# BigLCD_final_rev02.net
KiCad netlist of a schematic drawn in EAGLE
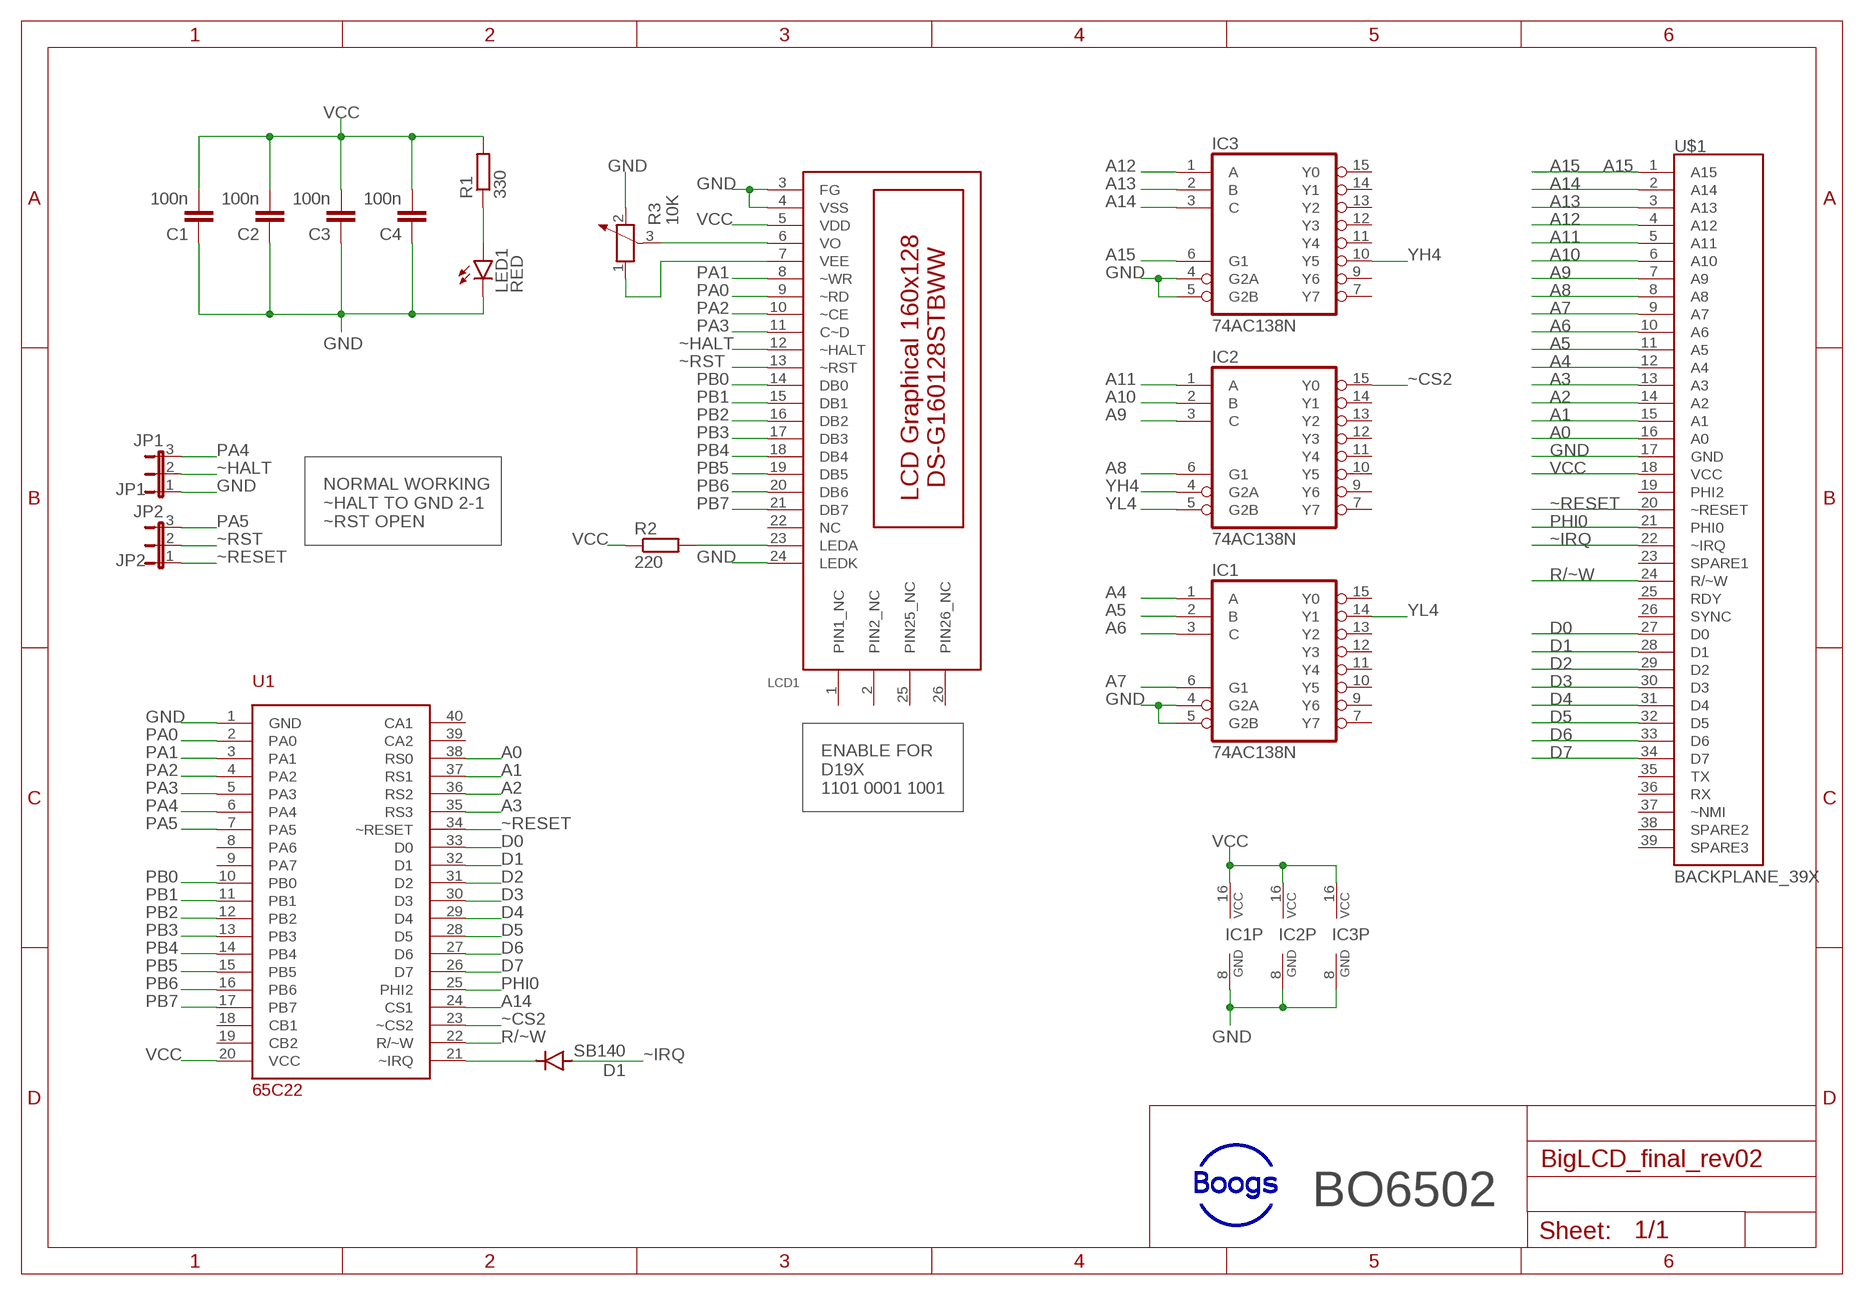
[diagram p0: schematic, sheet 1]

(export (version "E")
  (design (tool "Eeschema 10.0.6"))
  (components
    (comp (ref "C1")
      (value "100n")
      (footprint "eagle-import:C025-025X050")
      (libsource (lib "eagle-import") (part "C-EU025-025X050"))
    )
    (comp (ref "C2")
      (value "100n")
      (footprint "eagle-import:C025-025X050")
      (libsource (lib "eagle-import") (part "C-EU025-025X050"))
    )
    (comp (ref "C3")
      (value "100n")
      (footprint "eagle-import:C025-025X050")
      (libsource (lib "eagle-import") (part "C-EU025-025X050"))
    )
    (comp (ref "C4")
      (value "100n")
      (footprint "eagle-import:C025-025X050")
      (libsource (lib "eagle-import") (part "C-EU025-025X050"))
    )
    (comp (ref "D1")
      (value "SB140")
      (footprint "eagle-import:DO41-10")
      (libsource (lib "eagle-import") (part "1N4004"))
    )
    (comp (ref "IC1")
      (value "74AC138N")
      (footprint "eagle-import:DIL16")
      (libsource (lib "eagle-import") (part "74138NAC"))
    )
    (comp (ref "IC2")
      (value "74AC138N")
      (footprint "eagle-import:DIL16")
      (libsource (lib "eagle-import") (part "74138NAC"))
    )
    (comp (ref "IC3")
      (value "74AC138N")
      (footprint "eagle-import:DIL16")
      (libsource (lib "eagle-import") (part "74138NAC"))
    )
    (comp (ref "JP1")
      (value "JP1")
      (footprint "eagle-import:JP2")
      (libsource (lib "eagle-import") (part "JP2E"))
    )
    (comp (ref "JP2")
      (value "JP2")
      (footprint "eagle-import:JP2")
      (libsource (lib "eagle-import") (part "JP2E"))
    )
    (comp (ref "LCD1")
      (value "DS-G160128STBWW")
      (footprint "eagle-import:PAK100_2500-26")
      (libsource (lib "eagle-import") (part "DS-G160128STBWW"))
    )
    (comp (ref "LED1")
      (value "RED")
      (footprint "eagle-import:LED5MM")
      (libsource (lib "eagle-import") (part "LED5MM"))
    )
    (comp (ref "R1")
      (value "330")
      (footprint "eagle-import:0207_10")
      (libsource (lib "eagle-import") (part "R-EU_0207/10"))
    )
    (comp (ref "R2")
      (value "220")
      (footprint "eagle-import:0207_10")
      (libsource (lib "eagle-import") (part "R-EU_0207/10"))
    )
    (comp (ref "R3")
      (value "10K")
      (footprint "eagle-import:PT-10")
      (libsource (lib "eagle-import") (part "POTENTIOMETER_PT-10"))
    )
    (comp (ref "U$1")
      (value "BACKPLANE_39X")
      (footprint "eagle-import:BP_39X")
      (fields (field (name "A15") "A15"))
      (libsource (lib "eagle-import") (part "BACKPLANE_39X"))
    )
    (comp (ref "U1")
      (value "65C22")
      (footprint "eagle-import:DIL40")
      (libsource (lib "eagle-import") (part "65C22"))
    )
  )
  (nets
    (net (code "1") (name "/A0") (class "Default")
      (node (ref "U$1") (pin "16") (pinfunction "A0_16") (pintype "bidirectional"))
      (node (ref "U1") (pin "38") (pinfunction "RS0_38") (pintype "bidirectional"))
    )
    (net (code "2") (name "/A1") (class "Default")
      (node (ref "U$1") (pin "15") (pinfunction "A1_15") (pintype "bidirectional"))
      (node (ref "U1") (pin "37") (pinfunction "RS1_37") (pintype "bidirectional"))
    )
    (net (code "3") (name "/A2") (class "Default")
      (node (ref "U$1") (pin "14") (pinfunction "A2_14") (pintype "bidirectional"))
      (node (ref "U1") (pin "36") (pinfunction "RS2_36") (pintype "bidirectional"))
    )
    (net (code "4") (name "/A3") (class "Default")
      (node (ref "U$1") (pin "13") (pinfunction "A3_13") (pintype "bidirectional"))
      (node (ref "U1") (pin "35") (pinfunction "RS3_35") (pintype "bidirectional"))
    )
    (net (code "5") (name "/A4") (class "Default")
      (node (ref "IC1") (pin "1") (pinfunction "A_1") (pintype "input"))
      (node (ref "U$1") (pin "12") (pinfunction "A4_12") (pintype "bidirectional"))
    )
    (net (code "6") (name "/A5") (class "Default")
      (node (ref "IC1") (pin "2") (pinfunction "B_2") (pintype "input"))
      (node (ref "U$1") (pin "11") (pinfunction "A5_11") (pintype "bidirectional"))
    )
    (net (code "7") (name "/A6") (class "Default")
      (node (ref "IC1") (pin "3") (pinfunction "C_3") (pintype "input"))
      (node (ref "U$1") (pin "10") (pinfunction "A6_10") (pintype "bidirectional"))
    )
    (net (code "8") (name "/A7") (class "Default")
      (node (ref "IC1") (pin "6") (pinfunction "G1_6") (pintype "input"))
      (node (ref "U$1") (pin "9") (pinfunction "A7_9") (pintype "bidirectional"))
    )
    (net (code "9") (name "/A8") (class "Default")
      (node (ref "IC2") (pin "6") (pinfunction "G1_6") (pintype "input"))
      (node (ref "U$1") (pin "8") (pinfunction "A8_8") (pintype "bidirectional"))
    )
    (net (code "10") (name "/A9") (class "Default")
      (node (ref "IC2") (pin "3") (pinfunction "C_3") (pintype "input"))
      (node (ref "U$1") (pin "7") (pinfunction "A9_7") (pintype "bidirectional"))
    )
    (net (code "11") (name "/A10") (class "Default")
      (node (ref "IC2") (pin "2") (pinfunction "B_2") (pintype "input"))
      (node (ref "U$1") (pin "6") (pinfunction "A10_6") (pintype "bidirectional"))
    )
    (net (code "12") (name "/A11") (class "Default")
      (node (ref "IC2") (pin "1") (pinfunction "A_1") (pintype "input"))
      (node (ref "U$1") (pin "5") (pinfunction "A11_5") (pintype "bidirectional"))
    )
    (net (code "13") (name "/A12") (class "Default")
      (node (ref "IC3") (pin "1") (pinfunction "A_1") (pintype "input"))
      (node (ref "U$1") (pin "4") (pinfunction "A12_4") (pintype "bidirectional"))
    )
    (net (code "14") (name "/A13") (class "Default")
      (node (ref "IC3") (pin "2") (pinfunction "B_2") (pintype "input"))
      (node (ref "U$1") (pin "3") (pinfunction "A13_3") (pintype "bidirectional"))
    )
    (net (code "15") (name "/A14") (class "Default")
      (node (ref "IC3") (pin "3") (pinfunction "C_3") (pintype "input"))
      (node (ref "U$1") (pin "2") (pinfunction "A14_2") (pintype "bidirectional"))
      (node (ref "U1") (pin "24") (pinfunction "CS1_24") (pintype "bidirectional"))
    )
    (net (code "16") (name "/A15") (class "Default")
      (node (ref "IC3") (pin "6") (pinfunction "G1_6") (pintype "input"))
      (node (ref "U$1") (pin "1") (pinfunction "A15_1") (pintype "bidirectional"))
    )
    (net (code "17") (name "/D0") (class "Default")
      (node (ref "U$1") (pin "27") (pinfunction "D0_27") (pintype "bidirectional"))
      (node (ref "U1") (pin "33") (pinfunction "D0_33") (pintype "bidirectional"))
    )
    (net (code "18") (name "/D1") (class "Default")
      (node (ref "U$1") (pin "28") (pinfunction "D1_28") (pintype "bidirectional"))
      (node (ref "U1") (pin "32") (pinfunction "D1_32") (pintype "bidirectional"))
    )
    (net (code "19") (name "/D2") (class "Default")
      (node (ref "U$1") (pin "29") (pinfunction "D2_29") (pintype "bidirectional"))
      (node (ref "U1") (pin "31") (pinfunction "D2_31") (pintype "bidirectional"))
    )
    (net (code "20") (name "/D3") (class "Default")
      (node (ref "U$1") (pin "30") (pinfunction "D3_30") (pintype "bidirectional"))
      (node (ref "U1") (pin "30") (pinfunction "D3_30") (pintype "bidirectional"))
    )
    (net (code "21") (name "/D4") (class "Default")
      (node (ref "U$1") (pin "31") (pinfunction "D4_31") (pintype "bidirectional"))
      (node (ref "U1") (pin "29") (pinfunction "D4_29") (pintype "bidirectional"))
    )
    (net (code "22") (name "/D5") (class "Default")
      (node (ref "U$1") (pin "32") (pinfunction "D5_32") (pintype "bidirectional"))
      (node (ref "U1") (pin "28") (pinfunction "D5_28") (pintype "bidirectional"))
    )
    (net (code "23") (name "/D6") (class "Default")
      (node (ref "U$1") (pin "33") (pinfunction "D6_33") (pintype "bidirectional"))
      (node (ref "U1") (pin "27") (pinfunction "D6_27") (pintype "bidirectional"))
    )
    (net (code "24") (name "/D7") (class "Default")
      (node (ref "U$1") (pin "34") (pinfunction "D7_34") (pintype "bidirectional"))
      (node (ref "U1") (pin "26") (pinfunction "D7_26") (pintype "bidirectional"))
    )
    (net (code "25") (name "/GND") (class "Default")
      (node (ref "C1") (pin "1") (pinfunction "1_1") (pintype "passive"))
      (node (ref "C2") (pin "1") (pinfunction "1_1") (pintype "passive"))
      (node (ref "C3") (pin "1") (pinfunction "1_1") (pintype "passive"))
      (node (ref "C4") (pin "1") (pinfunction "1_1") (pintype "passive"))
      (node (ref "IC1") (pin "4") (pinfunction "G2A_4") (pintype "input"))
      (node (ref "IC1") (pin "5") (pinfunction "G2B_5") (pintype "input"))
      (node (ref "IC1") (pin "8") (pinfunction "GND_8") (pintype "power_in"))
      (node (ref "IC2") (pin "8") (pinfunction "GND_8") (pintype "power_in"))
      (node (ref "IC3") (pin "4") (pinfunction "G2A_4") (pintype "input"))
      (node (ref "IC3") (pin "5") (pinfunction "G2B_5") (pintype "input"))
      (node (ref "IC3") (pin "8") (pinfunction "GND_8") (pintype "power_in"))
      (node (ref "JP1") (pin "1") (pinfunction "1_1") (pintype "passive"))
      (node (ref "LCD1") (pin "24") (pinfunction "LEDK_24") (pintype "power_in"))
      (node (ref "LCD1") (pin "3") (pinfunction "FG_3") (pintype "input"))
      (node (ref "LCD1") (pin "4") (pinfunction "VSS_4") (pintype "power_in"))
      (node (ref "LED1") (pin "K") (pinfunction "C_K") (pintype "passive"))
      (node (ref "R3") (pin "2") (pinfunction "2_2") (pintype "passive"))
      (node (ref "U$1") (pin "17") (pinfunction "GND_17") (pintype "bidirectional"))
      (node (ref "U1") (pin "1") (pinfunction "GND_1") (pintype "bidirectional"))
    )
    (net (code "26") (name "/PA0") (class "Default")
      (node (ref "LCD1") (pin "9") (pinfunction "~{RD}_9") (pintype "bidirectional"))
      (node (ref "U1") (pin "2") (pinfunction "PA0_2") (pintype "bidirectional"))
    )
    (net (code "27") (name "/PA1") (class "Default")
      (node (ref "LCD1") (pin "8") (pinfunction "~{WR}_8") (pintype "input"))
      (node (ref "U1") (pin "3") (pinfunction "PA1_3") (pintype "bidirectional"))
    )
    (net (code "28") (name "/PA2") (class "Default")
      (node (ref "LCD1") (pin "10") (pinfunction "~{CE}_10") (pintype "bidirectional"))
      (node (ref "U1") (pin "4") (pinfunction "PA2_4") (pintype "bidirectional"))
    )
    (net (code "29") (name "/PA3") (class "Default")
      (node (ref "LCD1") (pin "11") (pinfunction "C~{D}_11") (pintype "bidirectional"))
      (node (ref "U1") (pin "5") (pinfunction "PA3_5") (pintype "bidirectional"))
    )
    (net (code "30") (name "/PA4") (class "Default")
      (node (ref "JP1") (pin "3") (pinfunction "3_3") (pintype "passive"))
      (node (ref "U1") (pin "6") (pinfunction "PA4_6") (pintype "bidirectional"))
    )
    (net (code "31") (name "/PA5") (class "Default")
      (node (ref "JP2") (pin "3") (pinfunction "3_3") (pintype "passive"))
      (node (ref "U1") (pin "7") (pinfunction "PA5_7") (pintype "bidirectional"))
    )
    (net (code "32") (name "/PB0") (class "Default")
      (node (ref "LCD1") (pin "14") (pinfunction "DB0_14") (pintype "input"))
      (node (ref "U1") (pin "10") (pinfunction "PB0_10") (pintype "bidirectional"))
    )
    (net (code "33") (name "/PB1") (class "Default")
      (node (ref "LCD1") (pin "15") (pinfunction "DB1_15") (pintype "input"))
      (node (ref "U1") (pin "11") (pinfunction "PB1_11") (pintype "bidirectional"))
    )
    (net (code "34") (name "/PB2") (class "Default")
      (node (ref "LCD1") (pin "16") (pinfunction "DB2_16") (pintype "input"))
      (node (ref "U1") (pin "12") (pinfunction "PB2_12") (pintype "bidirectional"))
    )
    (net (code "35") (name "/PB3") (class "Default")
      (node (ref "LCD1") (pin "17") (pinfunction "DB3_17") (pintype "input"))
      (node (ref "U1") (pin "13") (pinfunction "PB3_13") (pintype "bidirectional"))
    )
    (net (code "36") (name "/PB4") (class "Default")
      (node (ref "LCD1") (pin "18") (pinfunction "DB4_18") (pintype "input"))
      (node (ref "U1") (pin "14") (pinfunction "PB4_14") (pintype "bidirectional"))
    )
    (net (code "37") (name "/PB5") (class "Default")
      (node (ref "LCD1") (pin "19") (pinfunction "DB5_19") (pintype "input"))
      (node (ref "U1") (pin "15") (pinfunction "PB5_15") (pintype "bidirectional"))
    )
    (net (code "38") (name "/PB6") (class "Default")
      (node (ref "LCD1") (pin "20") (pinfunction "DB6_20") (pintype "input"))
      (node (ref "U1") (pin "16") (pinfunction "PB6_16") (pintype "bidirectional"))
    )
    (net (code "39") (name "/PB7") (class "Default")
      (node (ref "LCD1") (pin "21") (pinfunction "DB7_21") (pintype "input"))
      (node (ref "U1") (pin "17") (pinfunction "PB7_17") (pintype "bidirectional"))
    )
    (net (code "40") (name "/PHI0") (class "Default")
      (node (ref "U$1") (pin "21") (pinfunction "PHI0_21") (pintype "bidirectional"))
      (node (ref "U1") (pin "25") (pinfunction "PHI2_25") (pintype "bidirectional"))
    )
    (net (code "41") (name "/R{slash}~{W}") (class "Default")
      (node (ref "U$1") (pin "24") (pinfunction "R/~{W}_24") (pintype "bidirectional"))
      (node (ref "U1") (pin "22") (pinfunction "R/~{W}_22") (pintype "bidirectional"))
    )
    (net (code "42") (name "/VCC") (class "Default")
      (node (ref "C1") (pin "2") (pinfunction "2_2") (pintype "passive"))
      (node (ref "C2") (pin "2") (pinfunction "2_2") (pintype "passive"))
      (node (ref "C3") (pin "2") (pinfunction "2_2") (pintype "passive"))
      (node (ref "C4") (pin "2") (pinfunction "2_2") (pintype "passive"))
      (node (ref "IC1") (pin "16") (pinfunction "VCC_16") (pintype "power_in"))
      (node (ref "IC2") (pin "16") (pinfunction "VCC_16") (pintype "power_in"))
      (node (ref "IC3") (pin "16") (pinfunction "VCC_16") (pintype "power_in"))
      (node (ref "LCD1") (pin "5") (pinfunction "VDD_5") (pintype "power_in"))
      (node (ref "R1") (pin "2") (pinfunction "2_2") (pintype "passive"))
      (node (ref "R2") (pin "1") (pinfunction "1_1") (pintype "passive"))
      (node (ref "U$1") (pin "18") (pinfunction "VCC_18") (pintype "bidirectional"))
      (node (ref "U1") (pin "20") (pinfunction "VCC_20") (pintype "bidirectional"))
    )
    (net (code "43") (name "/YH4") (class "Default")
      (node (ref "IC2") (pin "4") (pinfunction "G2A_4") (pintype "input"))
      (node (ref "IC3") (pin "10") (pinfunction "Y5_10") (pintype "output"))
    )
    (net (code "44") (name "/YL4") (class "Default")
      (node (ref "IC1") (pin "14") (pinfunction "Y1_14") (pintype "output"))
      (node (ref "IC2") (pin "5") (pinfunction "G2B_5") (pintype "input"))
    )
    (net (code "45") (name "/~{CS2}") (class "Default")
      (node (ref "IC2") (pin "15") (pinfunction "Y0_15") (pintype "output"))
      (node (ref "U1") (pin "23") (pinfunction "~{CS2}_23") (pintype "bidirectional"))
    )
    (net (code "46") (name "/~{HALT}") (class "Default")
      (node (ref "JP1") (pin "2") (pinfunction "2_2") (pintype "passive"))
      (node (ref "LCD1") (pin "12") (pinfunction "~{HALT}_12") (pintype "bidirectional"))
    )
    (net (code "47") (name "/~{IRQ}") (class "Default")
      (node (ref "D1") (pin "A") (pinfunction "A_A") (pintype "passive"))
      (node (ref "U$1") (pin "22") (pinfunction "~{IRQ}_22") (pintype "bidirectional"))
    )
    (net (code "48") (name "/~{RESET}") (class "Default")
      (node (ref "JP2") (pin "1") (pinfunction "1_1") (pintype "passive"))
      (node (ref "U$1") (pin "20") (pinfunction "~{RESET}_20") (pintype "bidirectional"))
      (node (ref "U1") (pin "34") (pinfunction "~{RESET}_34") (pintype "bidirectional"))
    )
    (net (code "49") (name "/~{RST}") (class "Default")
      (node (ref "JP2") (pin "2") (pinfunction "2_2") (pintype "passive"))
      (node (ref "LCD1") (pin "13") (pinfunction "~{RST}_13") (pintype "bidirectional"))
    )
    (net (code "50") (name "Net-(LCD1-LEDA)") (class "Default")
      (node (ref "LCD1") (pin "23") (pinfunction "LEDA_23") (pintype "power_in"))
      (node (ref "R2") (pin "2") (pinfunction "2_2") (pintype "passive"))
    )
    (net (code "51") (name "Net-(LCD1-VEE)") (class "Default")
      (node (ref "LCD1") (pin "7") (pinfunction "VEE_7") (pintype "power_in"))
      (node (ref "R3") (pin "1") (pinfunction "1_1") (pintype "passive"))
    )
    (net (code "52") (name "Net-(LCD1-VO)") (class "Default")
      (node (ref "LCD1") (pin "6") (pinfunction "VO_6") (pintype "power_in"))
      (node (ref "R3") (pin "3") (pinfunction "3_3") (pintype "passive"))
    )
    (net (code "53") (name "Net-(LED1-PadA)") (class "Default")
      (node (ref "LED1") (pin "A") (pinfunction "A_A") (pintype "passive"))
      (node (ref "R1") (pin "1") (pinfunction "1_1") (pintype "passive"))
    )
    (net (code "54") (name "Net-(U1-~{IRQ})") (class "Default")
      (node (ref "D1") (pin "C") (pinfunction "C_C") (pintype "passive"))
      (node (ref "U1") (pin "21") (pinfunction "~{IRQ}_21") (pintype "bidirectional"))
    )
    (net (code "55") (name "unconnected-(IC1A-Y0-Pad15)") (class "Default")
      (node (ref "IC1") (pin "15") (pinfunction "Y0_15") (pintype "output"))
    )
    (net (code "56") (name "unconnected-(IC1A-Y2-Pad13)") (class "Default")
      (node (ref "IC1") (pin "13") (pinfunction "Y2_13") (pintype "output"))
    )
    (net (code "57") (name "unconnected-(IC1A-Y3-Pad12)") (class "Default")
      (node (ref "IC1") (pin "12") (pinfunction "Y3_12") (pintype "output"))
    )
    (net (code "58") (name "unconnected-(IC1A-Y4-Pad11)") (class "Default")
      (node (ref "IC1") (pin "11") (pinfunction "Y4_11") (pintype "output"))
    )
    (net (code "59") (name "unconnected-(IC1A-Y5-Pad10)") (class "Default")
      (node (ref "IC1") (pin "10") (pinfunction "Y5_10") (pintype "output"))
    )
    (net (code "60") (name "unconnected-(IC1A-Y6-Pad9)") (class "Default")
      (node (ref "IC1") (pin "9") (pinfunction "Y6_9") (pintype "output"))
    )
    (net (code "61") (name "unconnected-(IC1A-Y7-Pad7)") (class "Default")
      (node (ref "IC1") (pin "7") (pinfunction "Y7_7") (pintype "output"))
    )
    (net (code "62") (name "unconnected-(IC2A-Y1-Pad14)") (class "Default")
      (node (ref "IC2") (pin "14") (pinfunction "Y1_14") (pintype "output"))
    )
    (net (code "63") (name "unconnected-(IC2A-Y2-Pad13)") (class "Default")
      (node (ref "IC2") (pin "13") (pinfunction "Y2_13") (pintype "output"))
    )
    (net (code "64") (name "unconnected-(IC2A-Y3-Pad12)") (class "Default")
      (node (ref "IC2") (pin "12") (pinfunction "Y3_12") (pintype "output"))
    )
    (net (code "65") (name "unconnected-(IC2A-Y4-Pad11)") (class "Default")
      (node (ref "IC2") (pin "11") (pinfunction "Y4_11") (pintype "output"))
    )
    (net (code "66") (name "unconnected-(IC2A-Y5-Pad10)") (class "Default")
      (node (ref "IC2") (pin "10") (pinfunction "Y5_10") (pintype "output"))
    )
    (net (code "67") (name "unconnected-(IC2A-Y6-Pad9)") (class "Default")
      (node (ref "IC2") (pin "9") (pinfunction "Y6_9") (pintype "output"))
    )
    (net (code "68") (name "unconnected-(IC2A-Y7-Pad7)") (class "Default")
      (node (ref "IC2") (pin "7") (pinfunction "Y7_7") (pintype "output"))
    )
    (net (code "69") (name "unconnected-(IC3A-Y0-Pad15)") (class "Default")
      (node (ref "IC3") (pin "15") (pinfunction "Y0_15") (pintype "output"))
    )
    (net (code "70") (name "unconnected-(IC3A-Y1-Pad14)") (class "Default")
      (node (ref "IC3") (pin "14") (pinfunction "Y1_14") (pintype "output"))
    )
    (net (code "71") (name "unconnected-(IC3A-Y2-Pad13)") (class "Default")
      (node (ref "IC3") (pin "13") (pinfunction "Y2_13") (pintype "output"))
    )
    (net (code "72") (name "unconnected-(IC3A-Y3-Pad12)") (class "Default")
      (node (ref "IC3") (pin "12") (pinfunction "Y3_12") (pintype "output"))
    )
    (net (code "73") (name "unconnected-(IC3A-Y4-Pad11)") (class "Default")
      (node (ref "IC3") (pin "11") (pinfunction "Y4_11") (pintype "output"))
    )
    (net (code "74") (name "unconnected-(IC3A-Y6-Pad9)") (class "Default")
      (node (ref "IC3") (pin "9") (pinfunction "Y6_9") (pintype "output"))
    )
    (net (code "75") (name "unconnected-(IC3A-Y7-Pad7)") (class "Default")
      (node (ref "IC3") (pin "7") (pinfunction "Y7_7") (pintype "output"))
    )
    (net (code "76") (name "unconnected-(LCD1-NC-Pad22)") (class "Default")
      (node (ref "LCD1") (pin "22") (pinfunction "NC_22") (pintype "no_connect"))
    )
    (net (code "77") (name "unconnected-(LCD1-PIN1_NC-Pad1)") (class "Default")
      (node (ref "LCD1") (pin "1") (pinfunction "PIN1_NC_1") (pintype "no_connect"))
    )
    (net (code "78") (name "unconnected-(LCD1-PIN2_NC-Pad2)") (class "Default")
      (node (ref "LCD1") (pin "2") (pinfunction "PIN2_NC_2") (pintype "no_connect"))
    )
    (net (code "79") (name "unconnected-(LCD1-PIN25_NC-Pad25)") (class "Default")
      (node (ref "LCD1") (pin "25") (pinfunction "PIN25_NC_25") (pintype "no_connect"))
    )
    (net (code "80") (name "unconnected-(LCD1-PIN26_NC-Pad26)") (class "Default")
      (node (ref "LCD1") (pin "26") (pinfunction "PIN26_NC_26") (pintype "no_connect"))
    )
    (net (code "81") (name "unconnected-(U$1-PHI2-Pad19)") (class "Default")
      (node (ref "U$1") (pin "19") (pinfunction "PHI2_19") (pintype "bidirectional"))
    )
    (net (code "82") (name "unconnected-(U$1-RDY-Pad25)") (class "Default")
      (node (ref "U$1") (pin "25") (pinfunction "RDY_25") (pintype "bidirectional"))
    )
    (net (code "83") (name "unconnected-(U$1-RX-Pad36)") (class "Default")
      (node (ref "U$1") (pin "36") (pinfunction "RX_36") (pintype "bidirectional"))
    )
    (net (code "84") (name "unconnected-(U$1-SPARE1-Pad23)") (class "Default")
      (node (ref "U$1") (pin "23") (pinfunction "SPARE1_23") (pintype "bidirectional"))
    )
    (net (code "85") (name "unconnected-(U$1-SPARE2-Pad38)") (class "Default")
      (node (ref "U$1") (pin "38") (pinfunction "SPARE2_38") (pintype "bidirectional"))
    )
    (net (code "86") (name "unconnected-(U$1-SPARE3-Pad39)") (class "Default")
      (node (ref "U$1") (pin "39") (pinfunction "SPARE3_39") (pintype "bidirectional"))
    )
    (net (code "87") (name "unconnected-(U$1-SYNC-Pad26)") (class "Default")
      (node (ref "U$1") (pin "26") (pinfunction "SYNC_26") (pintype "bidirectional"))
    )
    (net (code "88") (name "unconnected-(U$1-TX-Pad35)") (class "Default")
      (node (ref "U$1") (pin "35") (pinfunction "TX_35") (pintype "bidirectional"))
    )
    (net (code "89") (name "unconnected-(U$1-~{NMI}-Pad37)") (class "Default")
      (node (ref "U$1") (pin "37") (pinfunction "~{NMI}_37") (pintype "bidirectional"))
    )
    (net (code "90") (name "unconnected-(U1-CA1-Pad40)") (class "Default")
      (node (ref "U1") (pin "40") (pinfunction "CA1_40") (pintype "bidirectional"))
    )
    (net (code "91") (name "unconnected-(U1-CA2-Pad39)") (class "Default")
      (node (ref "U1") (pin "39") (pinfunction "CA2_39") (pintype "bidirectional"))
    )
    (net (code "92") (name "unconnected-(U1-CB1-Pad18)") (class "Default")
      (node (ref "U1") (pin "18") (pinfunction "CB1_18") (pintype "bidirectional"))
    )
    (net (code "93") (name "unconnected-(U1-CB2-Pad19)") (class "Default")
      (node (ref "U1") (pin "19") (pinfunction "CB2_19") (pintype "bidirectional"))
    )
    (net (code "94") (name "unconnected-(U1-PA6-Pad8)") (class "Default")
      (node (ref "U1") (pin "8") (pinfunction "PA6_8") (pintype "bidirectional"))
    )
    (net (code "95") (name "unconnected-(U1-PA7-Pad9)") (class "Default")
      (node (ref "U1") (pin "9") (pinfunction "PA7_9") (pintype "bidirectional"))
    )
  )
)
